# USB.net
KiCad netlist of a schematic drawn in Altium Designer
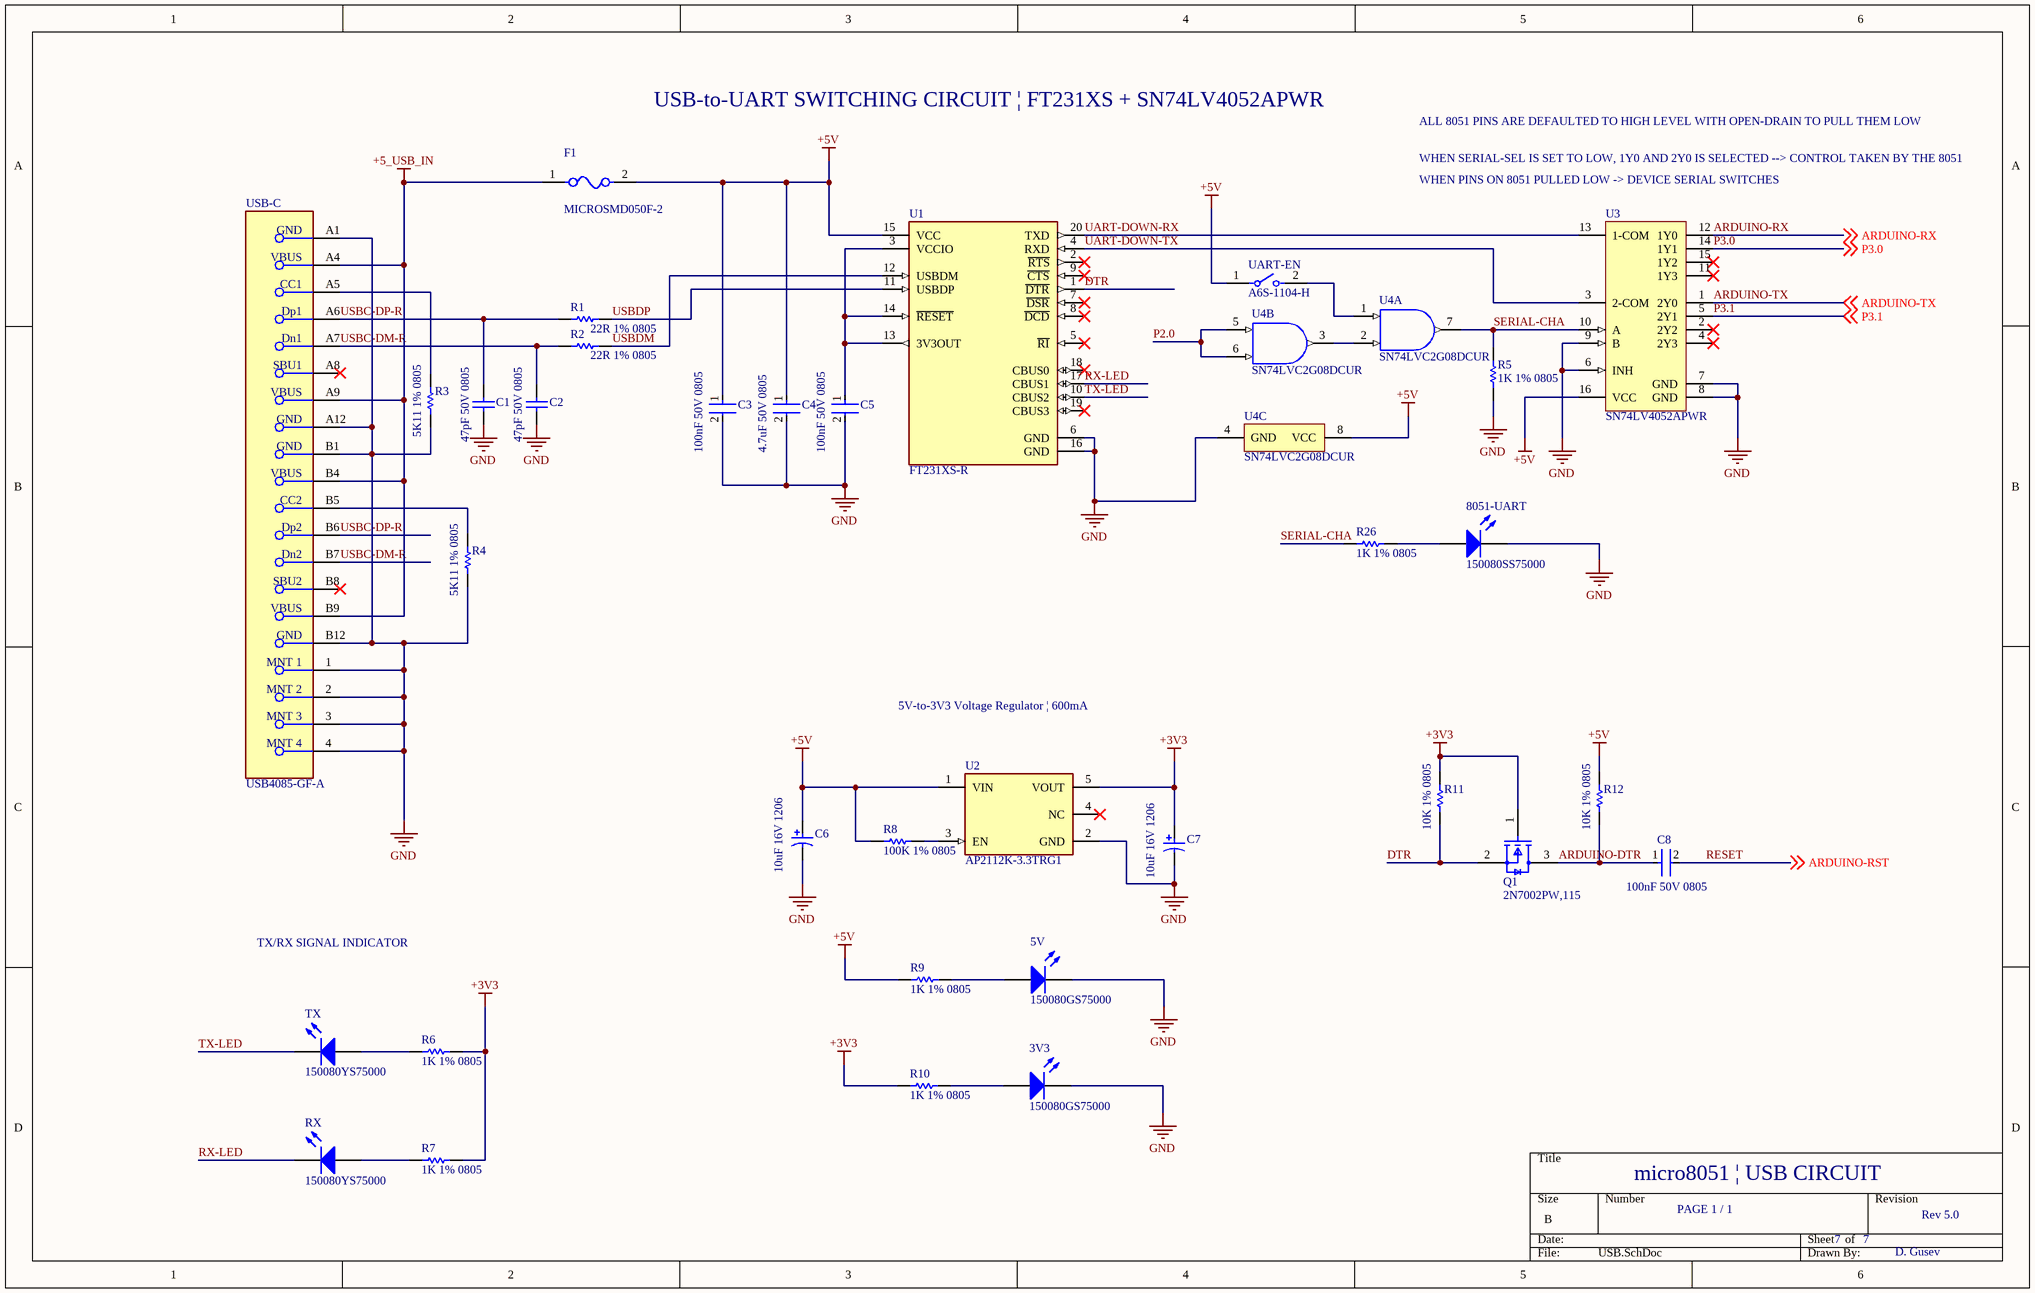
[diagram p0: USB.SchDoc]

(export (version "E")
  (design (tool "Eeschema 10.0.6"))
  (components
    (comp (ref "3V3")
      (value "150080GS75000")
      (footprint "0805_A")
      (description "SMD mono-color Chip LED, WL-SMCW, Green")
      (fields (field (name "MANUFACTURER") "Wuerth Elektronik"))
      (libsource (lib "Altium Content Vault") (part "WE-LED_K1A2-2"))
    )
    (comp (ref "5V")
      (value "150080GS75000")
      (footprint "0805_A")
      (description "SMD mono-color Chip LED, WL-SMCW, Green")
      (fields (field (name "MANUFACTURER") "Wuerth Elektronik"))
      (libsource (lib "Altium Content Vault") (part "WE-LED_K1A2-2"))
    )
    (comp (ref "8051-UART")
      (value "150080SS75000")
      (footprint "0805_A")
      (description "SMD mono-color Chip LED, WL-SMCW, Super Red")
      (fields (field (name "MANUFACTURER") "Wuerth Elektronik"))
      (libsource (lib "Altium Content Vault") (part "WE-LED_K1A2-2"))
    )
    (comp (ref "C1")
      (value "47pF 50V 0805")
      (footprint "CAPC2013X71X50NL20T25")
      (fields
        (field (name "PART NUMBER") "08055A470JAT2A")
        (field (name "MANUFACTURER") "AVX Interconnect / Elco")
      )
      (libsource (lib "Altium Content Vault") (part "CAP"))
    )
    (comp (ref "C2")
      (value "47pF 50V 0805")
      (footprint "CAPC2013X71X50NL20T25")
      (fields
        (field (name "PART NUMBER") "08055A470JAT2A")
        (field (name "MANUFACTURER") "AVX Interconnect / Elco")
      )
      (libsource (lib "Altium Content Vault") (part "CAP"))
    )
    (comp (ref "C3")
      (value "100nF 50V 0805")
      (footprint "FP-C0805C-DN-MFG")
      (description "CAP CER 0.1UF 50V X7R 0805")
      (fields
        (field (name "MANUFACTURER PART NUMBER") "C0805C104K5RACTU")
        (field (name "MANUFACTURER") "KEMET")
      )
      (libsource (lib "Altium Content Vault") (part "b4654b650e69147ec39a6b967a45e02"))
    )
    (comp (ref "C4")
      (value "4.7uF 50V 0805")
      (footprint "FP-C2012-125-MFG")
      (description "CAP CER 4.7UF 50V X5R 0805")
      (fields
        (field (name "TOLERANCE") "10%")
        (field (name "MANUFACTURER PART NUMBER") "C2012X5R1H475K125AB")
      )
      (libsource (lib "Altium Content Vault") (part "11868f565c42a9108669ba33697ecf6"))
    )
    (comp (ref "C5")
      (value "100nF 50V 0805")
      (footprint "FP-C0805C-DN-MFG")
      (description "CAP CER 0.1UF 50V X7R 0805")
      (fields
        (field (name "MANUFACTURER PART NUMBER") "C0805C104K5RACTU")
        (field (name "MANUFACTURER") "KEMET")
      )
      (libsource (lib "Altium Content Vault") (part "b4654b650e69147ec39a6b967a45e02"))
    )
    (comp (ref "C6")
      (value "10uF 16V 1206")
      (footprint "KEMT-A-3216-18-2_M")
      (description "Capacitor, Tantalum, 10 uF, +/- 10%, 16 V, -55 to 125 degC, 2-Pin SMD (1206), RoHS, Tape and Reel")
      (fields (field (name "VOLTAGE") "16VDC") (field (name "MANUFACTURER") "Kemet"))
      (libsource (lib "Altium Content Vault") (part "CAP-P-2"))
    )
    (comp (ref "C7")
      (value "10uF 16V 1206")
      (footprint "KEMT-A-3216-18-2_M")
      (description "Capacitor, Tantalum, 10 uF, +/- 10%, 16 V, -55 to 125 degC, 2-Pin SMD (1206), RoHS, Tape and Reel")
      (fields (field (name "VOLTAGE") "16VDC") (field (name "MANUFACTURER") "Kemet"))
      (libsource (lib "Altium Content Vault") (part "CAP-P-2"))
    )
    (comp (ref "C8")
      (value "100nF 50V 0805")
      (footprint "FP-C0805C-DN-MFG")
      (description "CAP CER 0.1UF 50V X7R 0805")
      (fields
        (field (name "MANUFACTURER PART NUMBER") "C0805C104K5RACTU")
        (field (name "MANUFACTURER") "KEMET")
      )
      (libsource (lib "Altium Content Vault") (part "b4654b650e69147ec39a6b967a45e02"))
    )
    (comp (ref "F1")
      (value "MICROSMD050F-2")
      (footprint "FP-microSMD-MFG")
      (description "PTC RESET FUSE 13.2V 500MA 1210")
      (fields
        (field (name "MANUFACTURER") "Littelfuse")
        (field (name "OCTOPART") "https://octopart.com/microsmd050f-2-littelfuse-74214982")
      )
      (libsource (lib "Altium Content Vault") (part "5bcf9b9f640e542cf0359d10258e979"))
    )
    (comp (ref "Q1")
      (value "2N7002PW,115")
      (footprint "FP-SOT323-MFG")
      (description "MOSFET N-CH 60V 0.31A SOT323")
      (libsource (lib "Altium Content Vault") (part "3b9c635fedb024a5347a57b145af9cc"))
    )
    (comp (ref "R1")
      (value "22R 1% 0805")
      (footprint "RESC2013X70X40LL20T20")
      (fields (field (name "PART NUMBER") "ERJ6ENF22R0V") (field (name "MANUFACTURER") "Panasonic"))
      (libsource (lib "Altium Content Vault") (part "RES"))
    )
    (comp (ref "R2")
      (value "22R 1% 0805")
      (footprint "RESC2013X70X40LL20T20")
      (fields (field (name "PART NUMBER") "ERJ6ENF22R0V") (field (name "MANUFACTURER") "Panasonic"))
      (libsource (lib "Altium Content Vault") (part "RES"))
    )
    (comp (ref "R3")
      (value "5K11 1% 0805")
      (footprint "RESC0805(2012)_N")
      (description "5K11 0.125W 1% 0805 (2012 Metric)  SMD")
      (fields (field (name "TOLERANCE") "1 %") (field (name "POWER") "0.125 W"))
      (libsource (lib "Altium Content Vault") (part "RES"))
    )
    (comp (ref "R4")
      (value "5K11 1% 0805")
      (footprint "RESC0805(2012)_N")
      (description "5K11 0.125W 1% 0805 (2012 Metric)  SMD")
      (fields (field (name "TOLERANCE") "1 %") (field (name "POWER") "0.125 W"))
      (libsource (lib "Altium Content Vault") (part "RES"))
    )
    (comp (ref "R5")
      (value "1K 1% 0805")
      (footprint "RESC2013X60X40ML20T25")
      (fields (field (name "PART NUMBER") "ERA6AEB123V") (field (name "MANUFACTURER") "Panasonic"))
      (libsource (lib "Altium Content Vault") (part "RES"))
    )
    (comp (ref "R6")
      (value "1K 1% 0805")
      (footprint "RESC2013X60X40ML20T25")
      (fields (field (name "PART NUMBER") "ERA6AEB123V") (field (name "MANUFACTURER") "Panasonic"))
      (libsource (lib "Altium Content Vault") (part "RES"))
    )
    (comp (ref "R7")
      (value "1K 1% 0805")
      (footprint "RESC2013X60X40ML20T25")
      (fields (field (name "PART NUMBER") "ERA6AEB123V") (field (name "MANUFACTURER") "Panasonic"))
      (libsource (lib "Altium Content Vault") (part "RES"))
    )
    (comp (ref "R8")
      (value "100K 1% 0805")
      (footprint "RESC2013X60X35ML10T20")
      (description "Chip Resistor, 100 KOhm, +/- 1%, 0.125 W, -55 to 155 degC, 0805 (2012 Metric), RoHS, Tape and Reel")
      (fields (field (name "MANUFACTURER") "Yageo") (field (name "TOLERANCE") "1%"))
      (libsource (lib "Altium Content Vault") (part "RES-2"))
    )
    (comp (ref "R9")
      (value "1K 1% 0805")
      (footprint "RESC2013X60X40ML20T25")
      (fields (field (name "PART NUMBER") "ERA6AEB123V") (field (name "MANUFACTURER") "Panasonic"))
      (libsource (lib "Altium Content Vault") (part "RES"))
    )
    (comp (ref "R10")
      (value "1K 1% 0805")
      (footprint "RESC2013X60X40ML20T25")
      (fields (field (name "PART NUMBER") "ERA6AEB123V") (field (name "MANUFACTURER") "Panasonic"))
      (libsource (lib "Altium Content Vault") (part "RES"))
    )
    (comp (ref "R11")
      (value "10K 1% 0805")
      (footprint "RESC2013X60X35NL10T20")
      (description "Chip Resistor, 10 KOhm, +/- 1%, 0.125 W, -55 to 155 degC, 0805 (2012 Metric), RoHS, Tape and Reel")
      (fields (field (name "MANUFACTURER") "Yageo"))
      (libsource (lib "Altium Content Vault") (part "RES-2"))
    )
    (comp (ref "R12")
      (value "10K 1% 0805")
      (footprint "RESC2013X60X35NL10T20")
      (description "Chip Resistor, 10 KOhm, +/- 1%, 0.125 W, -55 to 155 degC, 0805 (2012 Metric), RoHS, Tape and Reel")
      (fields (field (name "MANUFACTURER") "Yageo"))
      (libsource (lib "Altium Content Vault") (part "RES-2"))
    )
    (comp (ref "R26")
      (value "1K 1% 0805")
      (footprint "RESC2013X60X40ML20T25")
      (fields (field (name "PART NUMBER") "ERA6AEB123V") (field (name "MANUFACTURER") "Panasonic"))
      (libsource (lib "Altium Content Vault") (part "RES"))
    )
    (comp (ref "RX")
      (value "150080YS75000")
      (footprint "0805_A")
      (description "SMD mono-color Chip LED, WL-SMCW, Yellow")
      (fields (field (name "MANUFACTURER") "Wuerth Elektronik"))
      (libsource (lib "Altium Content Vault") (part "WE-LED_K1A2-2"))
    )
    (comp (ref "TX")
      (value "150080YS75000")
      (footprint "0805_A")
      (description "SMD mono-color Chip LED, WL-SMCW, Yellow")
      (fields (field (name "MANUFACTURER") "Wuerth Elektronik"))
      (libsource (lib "Altium Content Vault") (part "WE-LED_K1A2-2"))
    )
    (comp (ref "U1")
      (value "FT231XS-R")
      (footprint "FP-SSOP-20-MFG")
      (description "IC USB SERIAL FULL UART 20SSOP")
      (libsource (lib "Altium Content Vault") (part "6ea930917329caabf1041b50a9b81b2"))
    )
    (comp (ref "U2")
      (value "AP2112K-3.3TRG1")
      (footprint "FP-SOT25-IPC_A")
      (description "IC REG LINEAR 3.3V 600MA SOT25")
      (libsource (lib "Altium Content Vault") (part "c8ab751aee5229183125ab046a11caa"))
    )
    (comp (ref "U3")
      (value "SN74LV4052APWR")
      (footprint "PW0016A_M")
      (description "Dual 4-Channel Analog Multiplexer/Demultiplexer, PW0016A, LARGE T&R")
      (fields
        (field (name "GENERIC PART NUMBER") "SN74LV4052A")
        (field (name "MANUFACTURER") "Texas Instruments")
      )
      (libsource (lib "Altium Content Vault") (part "TI-SN74LV4052A-16"))
    )
    (comp (ref "U4")
      (value "SN74LVC2G08DCUR")
      (footprint "DCU0008A_M")
      (description "Dual 2-Input Positive-AND Gate, DCU0008A, LARGE T&R")
      (fields
        (field (name "MANUFACTURER") "Texas Instruments")
        (field (name "GENERIC PART NUMBER") "SN74LVC2G08")
      )
      (libsource (lib "") (part "TI-SN74XXX2G08-8_1"))
    )
    (comp (ref "UART-EN")
      (value "A6S-1104-H")
      (footprint "FP-A6S-1104-H-MFG")
      (description "SWITCH SLIDE DIP SPST 25MA 24V")
      (fields
        (field (name "MANUFACTURER") "Omron Electronics Inc-EMC Div")
        (field (name "OCTOPART") "https://octopart.com/a6s-1104-h-omron-55410938")
      )
      (libsource (lib "Altium Content Vault") (part "bb27bde45df87f1f469753f287ef5ae"))
    )
    (comp (ref "USB-C")
      (value "USB4085-GF-A")
      (footprint "FP-USB4085-GF-A-MFG")
      (description "CONN RCPT USB2.0 TYPEC 16POS")
      (fields
        (field (name "MANUFACTURER") "Global Connector Technology")
        (field (name "OCTOPART") "https://octopart.com/usb4085-gf-a-global+connector+technology-94773699")
      )
      (libsource (lib "Altium Content Vault") (part "f6997dba88850a18107ac0013977506"))
    )
  )
  (nets
    (net (code "1") (name "+3V3") (class "Default")
      (node (ref "C7") (pin "1") (pinfunction "1_1") (pintype "passive"))
      (node (ref "Q1") (pin "1") (pinfunction "G_1") (pintype "passive"))
      (node (ref "R10") (pin "2") (pinfunction "2_2") (pintype "passive"))
      (node (ref "R11") (pin "2") (pinfunction "2_2") (pintype "passive"))
      (node (ref "R6") (pin "1") (pinfunction "1_1") (pintype "passive"))
      (node (ref "R7") (pin "1") (pinfunction "1_1") (pintype "passive"))
      (node (ref "U2") (pin "5") (pinfunction "VOUT_5") (pintype "power_in"))
    )
    (net (code "2") (name "+5V") (class "Default")
      (node (ref "C3") (pin "1") (pinfunction "1_1") (pintype "passive"))
      (node (ref "C4") (pin "1") (pinfunction "1_1") (pintype "passive"))
      (node (ref "C6") (pin "1") (pinfunction "1_1") (pintype "passive"))
      (node (ref "F1") (pin "2") (pinfunction "2_2") (pintype "passive"))
      (node (ref "R12") (pin "2") (pinfunction "2_2") (pintype "passive"))
      (node (ref "R8") (pin "2") (pinfunction "2_2") (pintype "passive"))
      (node (ref "R9") (pin "2") (pinfunction "2_2") (pintype "passive"))
      (node (ref "U1") (pin "15") (pinfunction "VCC_15") (pintype "power_in"))
      (node (ref "U2") (pin "1") (pinfunction "VIN_1") (pintype "power_in"))
      (node (ref "U3") (pin "16") (pinfunction "VCC_16") (pintype "power_in"))
      (node (ref "U4") (pin "8") (pinfunction "VCC_8") (pintype "power_in"))
      (node (ref "UART-EN") (pin "1") (pinfunction "1_1") (pintype "passive"))
    )
    (net (code "3") (name "+5_USB_IN") (class "Default")
      (node (ref "F1") (pin "1") (pinfunction "1_1") (pintype "passive"))
      (node (ref "USB-C") (pin "A4") (pinfunction "VBUS_A4") (pintype "power_in"))
      (node (ref "USB-C") (pin "A9") (pinfunction "VBUS_A9") (pintype "power_in"))
      (node (ref "USB-C") (pin "B4") (pinfunction "VBUS_B4") (pintype "power_in"))
      (node (ref "USB-C") (pin "B9") (pinfunction "VBUS_B9") (pintype "power_in"))
    )
    (net (code "4") (name "/ARDUINO-DTR") (class "Default")
      (node (ref "C8") (pin "1") (pinfunction "1_1") (pintype "passive"))
      (node (ref "Q1") (pin "3") (pinfunction "D_3") (pintype "passive"))
      (node (ref "R12") (pin "1") (pinfunction "1_1") (pintype "passive"))
    )
    (net (code "5") (name "/DTR") (class "Default")
      (node (ref "Q1") (pin "2") (pinfunction "S_2") (pintype "passive"))
      (node (ref "R11") (pin "1") (pinfunction "1_1") (pintype "passive"))
      (node (ref "U1") (pin "1") (pinfunction "~{DTR}_1") (pintype "output"))
    )
    (net (code "6") (name "/P2.0") (class "Default")
      (node (ref "U4") (pin "5") (pinfunction "2A_5") (pintype "input"))
      (node (ref "U4") (pin "6") (pinfunction "2B_6") (pintype "input"))
    )
    (net (code "7") (name "/RX-LED") (class "Default")
      (node (ref "RX") (pin "1") (pinfunction "K_1") (pintype "passive"))
      (node (ref "U1") (pin "17") (pinfunction "CBUS1_17") (pintype "bidirectional"))
    )
    (net (code "8") (name "/SERIAL-CHA") (class "Default")
      (node (ref "R26") (pin "1") (pinfunction "1_1") (pintype "passive"))
      (node (ref "R5") (pin "1") (pinfunction "1_1") (pintype "passive"))
      (node (ref "U3") (pin "10") (pinfunction "A_10") (pintype "input"))
      (node (ref "U4") (pin "7") (pinfunction "1Y_7") (pintype "output"))
    )
    (net (code "9") (name "/TX-LED") (class "Default")
      (node (ref "TX") (pin "1") (pinfunction "K_1") (pintype "passive"))
      (node (ref "U1") (pin "10") (pinfunction "CBUS2_10") (pintype "bidirectional"))
    )
    (net (code "10") (name "/UART-DOWN-RX") (class "Default")
      (node (ref "U1") (pin "20") (pinfunction "TXD_20") (pintype "output"))
      (node (ref "U3") (pin "13") (pinfunction "1-COM_13") (pintype "passive"))
    )
    (net (code "11") (name "/UART-DOWN-TX") (class "Default")
      (node (ref "U1") (pin "4") (pinfunction "RXD_4") (pintype "input"))
      (node (ref "U3") (pin "3") (pinfunction "2-COM_3") (pintype "passive"))
    )
    (net (code "12") (name "/USBC-DM-R") (class "Default")
      (node (ref "C2") (pin "2") (pinfunction "2_2") (pintype "passive"))
      (node (ref "R2") (pin "1") (pinfunction "1_1") (pintype "passive"))
      (node (ref "USB-C") (pin "A7") (pinfunction "Dn1_A7") (pintype "passive"))
      (node (ref "USB-C") (pin "B7") (pinfunction "Dn2_B7") (pintype "passive"))
    )
    (net (code "13") (name "/USBC-DP-R") (class "Default")
      (node (ref "C1") (pin "2") (pinfunction "2_2") (pintype "passive"))
      (node (ref "R1") (pin "1") (pinfunction "1_1") (pintype "passive"))
      (node (ref "USB-C") (pin "A6") (pinfunction "Dp1_A6") (pintype "passive"))
      (node (ref "USB-C") (pin "B6") (pinfunction "Dp2_B6") (pintype "passive"))
    )
    (net (code "14") (name "/USBDM") (class "Default")
      (node (ref "R2") (pin "2") (pinfunction "2_2") (pintype "passive"))
      (node (ref "U1") (pin "12") (pinfunction "USBDM_12") (pintype "input"))
    )
    (net (code "15") (name "/USBDP") (class "Default")
      (node (ref "R1") (pin "2") (pinfunction "2_2") (pintype "passive"))
      (node (ref "U1") (pin "11") (pinfunction "USBDP_11") (pintype "input"))
    )
    (net (code "16") (name "ARDUINO-RST") (class "Default")
      (node (ref "C8") (pin "2") (pinfunction "2_2") (pintype "passive"))
    )
    (net (code "17") (name "ARDUINO-RX") (class "Default")
      (node (ref "U3") (pin "12") (pinfunction "1Y0_12") (pintype "passive"))
    )
    (net (code "18") (name "ARDUINO-TX") (class "Default")
      (node (ref "U3") (pin "1") (pinfunction "2Y0_1") (pintype "passive"))
    )
    (net (code "19") (name "GND") (class "Default")
      (node (ref "3V3") (pin "1") (pinfunction "K_1") (pintype "passive"))
      (node (ref "5V") (pin "1") (pinfunction "K_1") (pintype "passive"))
      (node (ref "8051-UART") (pin "1") (pinfunction "K_1") (pintype "passive"))
      (node (ref "C1") (pin "1") (pinfunction "1_1") (pintype "passive"))
      (node (ref "C2") (pin "1") (pinfunction "1_1") (pintype "passive"))
      (node (ref "C3") (pin "2") (pinfunction "2_2") (pintype "passive"))
      (node (ref "C4") (pin "2") (pinfunction "2_2") (pintype "passive"))
      (node (ref "C5") (pin "2") (pinfunction "2_2") (pintype "passive"))
      (node (ref "C6") (pin "2") (pinfunction "2_2") (pintype "passive"))
      (node (ref "C7") (pin "2") (pinfunction "2_2") (pintype "passive"))
      (node (ref "R3") (pin "1") (pinfunction "1_1") (pintype "passive"))
      (node (ref "R4") (pin "1") (pinfunction "1_1") (pintype "passive"))
      (node (ref "R5") (pin "2") (pinfunction "2_2") (pintype "passive"))
      (node (ref "U1") (pin "16") (pinfunction "GND_16") (pintype "power_in"))
      (node (ref "U1") (pin "6") (pinfunction "GND_6") (pintype "power_in"))
      (node (ref "U2") (pin "2") (pinfunction "GND_2") (pintype "power_in"))
      (node (ref "U3") (pin "6") (pinfunction "INH_6") (pintype "input"))
      (node (ref "U3") (pin "7") (pinfunction "GND_7") (pintype "power_in"))
      (node (ref "U3") (pin "8") (pinfunction "GND_8") (pintype "power_in"))
      (node (ref "U3") (pin "9") (pinfunction "B_9") (pintype "input"))
      (node (ref "U4") (pin "4") (pinfunction "GND_4") (pintype "power_in"))
      (node (ref "USB-C") (pin "1") (pinfunction "MNT_1_1") (pintype "passive"))
      (node (ref "USB-C") (pin "2") (pinfunction "MNT_2_2") (pintype "passive"))
      (node (ref "USB-C") (pin "3") (pinfunction "MNT_3_3") (pintype "passive"))
      (node (ref "USB-C") (pin "4") (pinfunction "MNT_4_4") (pintype "passive"))
      (node (ref "USB-C") (pin "A1") (pinfunction "GND_A1") (pintype "power_in"))
      (node (ref "USB-C") (pin "A12") (pinfunction "GND_A12") (pintype "power_in"))
      (node (ref "USB-C") (pin "B1") (pinfunction "GND_B1") (pintype "power_in"))
      (node (ref "USB-C") (pin "B12") (pinfunction "GND_B12") (pintype "power_in"))
    )
    (net (code "20") (name "Net-(3V3-A)") (class "Default")
      (node (ref "3V3") (pin "2") (pinfunction "A_2") (pintype "passive"))
      (node (ref "R10") (pin "1") (pinfunction "1_1") (pintype "passive"))
    )
    (net (code "21") (name "Net-(5V-A)") (class "Default")
      (node (ref "5V") (pin "2") (pinfunction "A_2") (pintype "passive"))
      (node (ref "R9") (pin "1") (pinfunction "1_1") (pintype "passive"))
    )
    (net (code "22") (name "Net-(8051-UART-A)") (class "Default")
      (node (ref "8051-UART") (pin "2") (pinfunction "A_2") (pintype "passive"))
      (node (ref "R26") (pin "2") (pinfunction "2_2") (pintype "passive"))
    )
    (net (code "23") (name "Net-(RX-A)") (class "Default")
      (node (ref "R7") (pin "2") (pinfunction "2_2") (pintype "passive"))
      (node (ref "RX") (pin "2") (pinfunction "A_2") (pintype "passive"))
    )
    (net (code "24") (name "Net-(TX-A)") (class "Default")
      (node (ref "R6") (pin "2") (pinfunction "2_2") (pintype "passive"))
      (node (ref "TX") (pin "2") (pinfunction "A_2") (pintype "passive"))
    )
    (net (code "25") (name "Net-(U1-3V3OUT)") (class "Default")
      (node (ref "C5") (pin "1") (pinfunction "1_1") (pintype "passive"))
      (node (ref "U1") (pin "13") (pinfunction "3V3OUT_13") (pintype "output"))
      (node (ref "U1") (pin "14") (pinfunction "~{RESET}_14") (pintype "input"))
      (node (ref "U1") (pin "3") (pinfunction "VCCIO_3") (pintype "power_in"))
    )
    (net (code "26") (name "Net-(U2-EN)") (class "Default")
      (node (ref "R8") (pin "1") (pinfunction "1_1") (pintype "passive"))
      (node (ref "U2") (pin "3") (pinfunction "EN_3") (pintype "input"))
    )
    (net (code "27") (name "Net-(U4A-1A)") (class "Default")
      (node (ref "U4") (pin "1") (pinfunction "1A_1") (pintype "input"))
      (node (ref "UART-EN") (pin "2") (pinfunction "2_2") (pintype "passive"))
    )
    (net (code "28") (name "Net-(U4A-1B)") (class "Default")
      (node (ref "U4") (pin "2") (pinfunction "1B_2") (pintype "input"))
      (node (ref "U4") (pin "3") (pinfunction "2Y_3") (pintype "output"))
    )
    (net (code "29") (name "Net-(USB-C-CC1)") (class "Default")
      (node (ref "R3") (pin "2") (pinfunction "2_2") (pintype "passive"))
      (node (ref "USB-C") (pin "A5") (pinfunction "CC1_A5") (pintype "passive"))
    )
    (net (code "30") (name "Net-(USB-C-CC2)") (class "Default")
      (node (ref "R4") (pin "2") (pinfunction "2_2") (pintype "passive"))
      (node (ref "USB-C") (pin "B5") (pinfunction "CC2_B5") (pintype "passive"))
    )
    (net (code "31") (name "P3.0") (class "Default")
      (node (ref "U3") (pin "14") (pinfunction "1Y1_14") (pintype "passive"))
    )
    (net (code "32") (name "P3.1") (class "Default")
      (node (ref "U3") (pin "5") (pinfunction "2Y1_5") (pintype "passive"))
    )
    (net (code "33") (name "unconnected-(U1-CBUS0-Pad18)") (class "Default")
      (node (ref "U1") (pin "18") (pinfunction "CBUS0_18") (pintype "bidirectional+no_connect"))
    )
    (net (code "34") (name "unconnected-(U1-CBUS3-Pad19)") (class "Default")
      (node (ref "U1") (pin "19") (pinfunction "CBUS3_19") (pintype "bidirectional+no_connect"))
    )
    (net (code "35") (name "unconnected-(U1-~{CTS}-Pad9)") (class "Default")
      (node (ref "U1") (pin "9") (pinfunction "~{CTS}_9") (pintype "input+no_connect"))
    )
    (net (code "36") (name "unconnected-(U1-~{DCD}-Pad8)") (class "Default")
      (node (ref "U1") (pin "8") (pinfunction "~{DCD}_8") (pintype "input+no_connect"))
    )
    (net (code "37") (name "unconnected-(U1-~{DSR}-Pad7)") (class "Default")
      (node (ref "U1") (pin "7") (pinfunction "~{DSR}_7") (pintype "input+no_connect"))
    )
    (net (code "38") (name "unconnected-(U1-~{RI}-Pad5)") (class "Default")
      (node (ref "U1") (pin "5") (pinfunction "~{RI}_5") (pintype "input+no_connect"))
    )
    (net (code "39") (name "unconnected-(U1-~{RTS}-Pad2)") (class "Default")
      (node (ref "U1") (pin "2") (pinfunction "~{RTS}_2") (pintype "output+no_connect"))
    )
    (net (code "40") (name "unconnected-(U2-NC-Pad4)") (class "Default")
      (node (ref "U2") (pin "4") (pinfunction "NC_4") (pintype "passive+no_connect"))
    )
    (net (code "41") (name "unconnected-(U3-1Y2-Pad15)") (class "Default")
      (node (ref "U3") (pin "15") (pinfunction "1Y2_15") (pintype "passive+no_connect"))
    )
    (net (code "42") (name "unconnected-(U3-1Y3-Pad11)") (class "Default")
      (node (ref "U3") (pin "11") (pinfunction "1Y3_11") (pintype "passive+no_connect"))
    )
    (net (code "43") (name "unconnected-(U3-2Y2-Pad2)") (class "Default")
      (node (ref "U3") (pin "2") (pinfunction "2Y2_2") (pintype "passive+no_connect"))
    )
    (net (code "44") (name "unconnected-(U3-2Y3-Pad4)") (class "Default")
      (node (ref "U3") (pin "4") (pinfunction "2Y3_4") (pintype "passive+no_connect"))
    )
    (net (code "45") (name "unconnected-(USB-C-SBU1-PadA8)") (class "Default")
      (node (ref "USB-C") (pin "A8") (pinfunction "SBU1_A8") (pintype "passive+no_connect"))
    )
    (net (code "46") (name "unconnected-(USB-C-SBU2-PadB8)") (class "Default")
      (node (ref "USB-C") (pin "B8") (pinfunction "SBU2_B8") (pintype "passive+no_connect"))
    )
  )
)
